# AND_GATE.net
KiCad netlist of a schematic drawn in Altium Designer
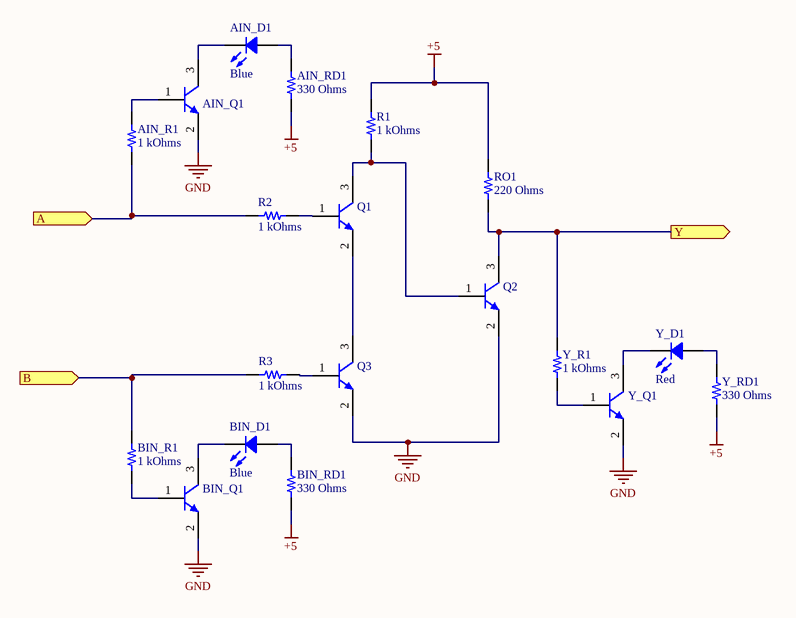
[diagram p0: AND_GATE.SchDoc]

(export (version "E")
  (design (tool "Eeschema 10.0.6"))
  (components
    (comp (ref "AIN_D1")
      (value "Blue")
      (footprint "LED 0603_1608 BLUE")
      (description "LED BLUE CLEAR 0603 SMD")
      (fields (field (name "PART NUMBER") "IN-S63AT5B") (field (name "MANUFACTURER") "Inolux"))
      (libsource (lib "Celestial Altium Library - altium_library") (part "LED"))
    )
    (comp (ref "AIN_Q1")
      (value "MMSS8050-L-TP")
      (footprint "MCCSEMI SOT-23-3")
      (description "TRANS NPN 25V 1.5A SOT23")
      (fields (field (name "MANUFACTURER") "Micro Commercial Co"))
      (libsource (lib "Celestial Altium Library - altium_library") (part "MCCSEMI NPN SOT-23-3"))
    )
    (comp (ref "AIN_R1")
      (value "1 kOhms")
      (footprint "RES 0603_1608")
      (description "RES SMD 1K OHM 0.1% 1/16W 0603")
      (fields
        (field (name "PART NUMBER") "CPF0603B1K0E")
        (field (name "MANUFACTURER") "TE Connectivity Passive Product")
      )
      (libsource (lib "Celestial Altium Library - altium_library") (part "Resistor"))
    )
    (comp (ref "AIN_RD1")
      (value "330 Ohms")
      (footprint "RES 0603_1608")
      (description "RES 330 OHM 5% 1/10W 0603")
      (fields
        (field (name "PART NUMBER") "RMCF0603JT330R")
        (field (name "MANUFACTURER") "Stackpole Electronics Inc")
      )
      (libsource (lib "Celestial Altium Library - altium_library") (part "Resistor"))
    )
    (comp (ref "BIN_D1")
      (value "Blue")
      (footprint "LED 0603_1608 BLUE")
      (description "LED BLUE CLEAR 0603 SMD")
      (fields (field (name "PART NUMBER") "IN-S63AT5B") (field (name "MANUFACTURER") "Inolux"))
      (libsource (lib "Celestial Altium Library - altium_library") (part "LED"))
    )
    (comp (ref "BIN_Q1")
      (value "MMSS8050-L-TP")
      (footprint "MCCSEMI SOT-23-3")
      (description "TRANS NPN 25V 1.5A SOT23")
      (fields (field (name "MANUFACTURER") "Micro Commercial Co"))
      (libsource (lib "Celestial Altium Library - altium_library") (part "MCCSEMI NPN SOT-23-3"))
    )
    (comp (ref "BIN_R1")
      (value "1 kOhms")
      (footprint "RES 0603_1608")
      (description "RES SMD 1K OHM 0.1% 1/16W 0603")
      (fields
        (field (name "PART NUMBER") "CPF0603B1K0E")
        (field (name "MANUFACTURER") "TE Connectivity Passive Product")
      )
      (libsource (lib "Celestial Altium Library - altium_library") (part "Resistor"))
    )
    (comp (ref "BIN_RD1")
      (value "330 Ohms")
      (footprint "RES 0603_1608")
      (description "RES 330 OHM 5% 1/10W 0603")
      (fields
        (field (name "PART NUMBER") "RMCF0603JT330R")
        (field (name "MANUFACTURER") "Stackpole Electronics Inc")
      )
      (libsource (lib "Celestial Altium Library - altium_library") (part "Resistor"))
    )
    (comp (ref "Q1")
      (value "MMSS8050-L-TP")
      (footprint "MCCSEMI SOT-23-3")
      (description "TRANS NPN 25V 1.5A SOT23")
      (fields (field (name "MANUFACTURER") "Micro Commercial Co"))
      (libsource (lib "Celestial Altium Library - altium_library") (part "MCCSEMI NPN SOT-23-3"))
    )
    (comp (ref "Q2")
      (value "MMSS8050-L-TP")
      (footprint "MCCSEMI SOT-23-3")
      (description "TRANS NPN 25V 1.5A SOT23")
      (fields (field (name "MANUFACTURER") "Micro Commercial Co"))
      (libsource (lib "Celestial Altium Library - altium_library") (part "MCCSEMI NPN SOT-23-3"))
    )
    (comp (ref "Q3")
      (value "MMSS8050-L-TP")
      (footprint "MCCSEMI SOT-23-3")
      (description "TRANS NPN 25V 1.5A SOT23")
      (fields (field (name "MANUFACTURER") "Micro Commercial Co"))
      (libsource (lib "Celestial Altium Library - altium_library") (part "MCCSEMI NPN SOT-23-3"))
    )
    (comp (ref "R1")
      (value "1 kOhms")
      (footprint "RES 0603_1608")
      (description "RES SMD 1K OHM 0.1% 1/16W 0603")
      (fields
        (field (name "PART NUMBER") "CPF0603B1K0E")
        (field (name "MANUFACTURER") "TE Connectivity Passive Product")
      )
      (libsource (lib "Celestial Altium Library - altium_library") (part "Resistor"))
    )
    (comp (ref "R2")
      (value "1 kOhms")
      (footprint "RES 0603_1608")
      (description "RES SMD 1K OHM 0.1% 1/16W 0603")
      (fields
        (field (name "PART NUMBER") "CPF0603B1K0E")
        (field (name "MANUFACTURER") "TE Connectivity Passive Product")
      )
      (libsource (lib "Celestial Altium Library - altium_library") (part "Resistor"))
    )
    (comp (ref "R3")
      (value "1 kOhms")
      (footprint "RES 0603_1608")
      (description "RES SMD 1K OHM 0.1% 1/16W 0603")
      (fields
        (field (name "PART NUMBER") "CPF0603B1K0E")
        (field (name "MANUFACTURER") "TE Connectivity Passive Product")
      )
      (libsource (lib "Celestial Altium Library - altium_library") (part "Resistor"))
    )
    (comp (ref "RO1")
      (value "220 Ohms")
      (footprint "RES 0603_1608")
      (description "RES SMD 220 OHM 0.5% 1/10W 0603")
      (fields
        (field (name "PART NUMBER") "ERA-3AED221V")
        (field (name "MANUFACTURER") "Panasonic Electronic Components")
      )
      (libsource (lib "Celestial Altium Library - altium_library") (part "Resistor"))
    )
    (comp (ref "Y_D1")
      (value "Red")
      (footprint "LED 0603_1608 RED")
      (description "LED RED CLEAR CHIP SMD")
      (fields (field (name "PART NUMBER") "XZMDK53W-8") (field (name "MANUFACTURER") "SunLED"))
      (libsource (lib "Celestial Altium Library - altium_library") (part "LED"))
    )
    (comp (ref "Y_Q1")
      (value "MMSS8050-L-TP")
      (footprint "MCCSEMI SOT-23-3")
      (description "TRANS NPN 25V 1.5A SOT23")
      (fields (field (name "MANUFACTURER") "Micro Commercial Co"))
      (libsource (lib "Celestial Altium Library - altium_library") (part "MCCSEMI NPN SOT-23-3"))
    )
    (comp (ref "Y_R1")
      (value "1 kOhms")
      (footprint "RES 0603_1608")
      (description "RES SMD 1K OHM 0.1% 1/16W 0603")
      (fields
        (field (name "PART NUMBER") "CPF0603B1K0E")
        (field (name "MANUFACTURER") "TE Connectivity Passive Product")
      )
      (libsource (lib "Celestial Altium Library - altium_library") (part "Resistor"))
    )
    (comp (ref "Y_RD1")
      (value "330 Ohms")
      (footprint "RES 0603_1608")
      (description "RES 330 OHM 5% 1/10W 0603")
      (fields
        (field (name "PART NUMBER") "RMCF0603JT330R")
        (field (name "MANUFACTURER") "Stackpole Electronics Inc")
      )
      (libsource (lib "Celestial Altium Library - altium_library") (part "Resistor"))
    )
  )
  (nets
    (net (code "1") (name "+5") (class "Default")
      (node (ref "AIN_RD1") (pin "1") (pinfunction "1_1") (pintype "passive"))
      (node (ref "BIN_RD1") (pin "1") (pinfunction "1_1") (pintype "passive"))
      (node (ref "R1") (pin "2") (pinfunction "2_2") (pintype "passive"))
      (node (ref "RO1") (pin "2") (pinfunction "2_2") (pintype "passive"))
      (node (ref "Y_RD1") (pin "1") (pinfunction "1_1") (pintype "passive"))
    )
    (net (code "2") (name "/A") (class "Default")
      (node (ref "AIN_R1") (pin "2") (pinfunction "2_2") (pintype "passive"))
      (node (ref "R2") (pin "1") (pinfunction "1_1") (pintype "passive"))
    )
    (net (code "3") (name "/B") (class "Default")
      (node (ref "BIN_R1") (pin "2") (pinfunction "2_2") (pintype "passive"))
      (node (ref "R3") (pin "1") (pinfunction "1_1") (pintype "passive"))
    )
    (net (code "4") (name "/Y") (class "Default")
      (node (ref "Q2") (pin "3") (pinfunction "C_3") (pintype "passive"))
      (node (ref "RO1") (pin "1") (pinfunction "1_1") (pintype "passive"))
      (node (ref "Y_R1") (pin "2") (pinfunction "2_2") (pintype "passive"))
    )
    (net (code "5") (name "GND") (class "Default")
      (node (ref "AIN_Q1") (pin "2") (pinfunction "E_2") (pintype "passive"))
      (node (ref "BIN_Q1") (pin "2") (pinfunction "E_2") (pintype "passive"))
      (node (ref "Q2") (pin "2") (pinfunction "E_2") (pintype "passive"))
      (node (ref "Q3") (pin "2") (pinfunction "E_2") (pintype "passive"))
      (node (ref "Y_Q1") (pin "2") (pinfunction "E_2") (pintype "passive"))
    )
    (net (code "6") (name "Net-(AIN_D1-Pad1)") (class "Default")
      (node (ref "AIN_D1") (pin "1") (pinfunction "1_1") (pintype "passive"))
      (node (ref "AIN_RD1") (pin "2") (pinfunction "2_2") (pintype "passive"))
    )
    (net (code "7") (name "Net-(AIN_Q1-B)") (class "Default")
      (node (ref "AIN_Q1") (pin "1") (pinfunction "B_1") (pintype "passive"))
      (node (ref "AIN_R1") (pin "1") (pinfunction "1_1") (pintype "passive"))
    )
    (net (code "8") (name "Net-(AIN_Q1-C)") (class "Default")
      (node (ref "AIN_D1") (pin "2") (pinfunction "2_2") (pintype "passive"))
      (node (ref "AIN_Q1") (pin "3") (pinfunction "C_3") (pintype "passive"))
    )
    (net (code "9") (name "Net-(BIN_D1-Pad1)") (class "Default")
      (node (ref "BIN_D1") (pin "1") (pinfunction "1_1") (pintype "passive"))
      (node (ref "BIN_RD1") (pin "2") (pinfunction "2_2") (pintype "passive"))
    )
    (net (code "10") (name "Net-(BIN_Q1-B)") (class "Default")
      (node (ref "BIN_Q1") (pin "1") (pinfunction "B_1") (pintype "passive"))
      (node (ref "BIN_R1") (pin "1") (pinfunction "1_1") (pintype "passive"))
    )
    (net (code "11") (name "Net-(BIN_Q1-C)") (class "Default")
      (node (ref "BIN_D1") (pin "2") (pinfunction "2_2") (pintype "passive"))
      (node (ref "BIN_Q1") (pin "3") (pinfunction "C_3") (pintype "passive"))
    )
    (net (code "12") (name "Net-(Q1-B)") (class "Default")
      (node (ref "Q1") (pin "1") (pinfunction "B_1") (pintype "passive"))
      (node (ref "R2") (pin "2") (pinfunction "2_2") (pintype "passive"))
    )
    (net (code "13") (name "Net-(Q1-C)") (class "Default")
      (node (ref "Q1") (pin "3") (pinfunction "C_3") (pintype "passive"))
      (node (ref "Q2") (pin "1") (pinfunction "B_1") (pintype "passive"))
      (node (ref "R1") (pin "1") (pinfunction "1_1") (pintype "passive"))
    )
    (net (code "14") (name "Net-(Q1-E)") (class "Default")
      (node (ref "Q1") (pin "2") (pinfunction "E_2") (pintype "passive"))
      (node (ref "Q3") (pin "3") (pinfunction "C_3") (pintype "passive"))
    )
    (net (code "15") (name "Net-(Q3-B)") (class "Default")
      (node (ref "Q3") (pin "1") (pinfunction "B_1") (pintype "passive"))
      (node (ref "R3") (pin "2") (pinfunction "2_2") (pintype "passive"))
    )
    (net (code "16") (name "Net-(Y_D1-Pad1)") (class "Default")
      (node (ref "Y_D1") (pin "1") (pinfunction "1_1") (pintype "passive"))
      (node (ref "Y_RD1") (pin "2") (pinfunction "2_2") (pintype "passive"))
    )
    (net (code "17") (name "Net-(Y_Q1-B)") (class "Default")
      (node (ref "Y_Q1") (pin "1") (pinfunction "B_1") (pintype "passive"))
      (node (ref "Y_R1") (pin "1") (pinfunction "1_1") (pintype "passive"))
    )
    (net (code "18") (name "Net-(Y_Q1-C)") (class "Default")
      (node (ref "Y_D1") (pin "2") (pinfunction "2_2") (pintype "passive"))
      (node (ref "Y_Q1") (pin "3") (pinfunction "C_3") (pintype "passive"))
    )
  )
)
